# Sd_sdio.net
KiCad netlist of a schematic drawn in Altium Designer
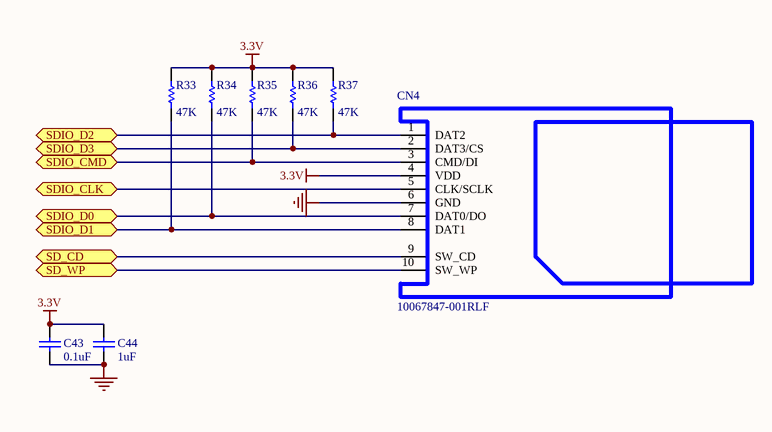
[diagram p0: Sd_sdio.SchDoc]

(export (version "E")
  (design (tool "Eeschema 10.0.6"))
  (components
    (comp (ref "C43")
      (value "0.1uF")
      (footprint "CAPC2012N")
      (description "Capacitor")
      (fields (field (name "Comment") "Cap"))
      (libsource (lib "Core429IBaseBoard") (part "Cap"))
    )
    (comp (ref "C44")
      (value "1uF")
      (footprint "CAPC3216N")
      (description "Capacitor")
      (fields (field (name "Comment") "Cap"))
      (libsource (lib "Core429IBaseBoard") (part "Cap"))
    )
    (comp (ref "CN4")
      (value "10067847-001RLF")
      (footprint "10067847")
      (description "SD Card Reader")
      (libsource (lib "Core429IBaseBoardVerE") (part "SD"))
    )
    (comp (ref "R33")
      (value "47K")
      (footprint "RESC2012N")
      (description "Resistor")
      (fields (field (name "Comment") "1206"))
      (libsource (lib "Core429IBaseBoard") (part "Res"))
    )
    (comp (ref "R34")
      (value "47K")
      (footprint "RESC2012N")
      (description "Resistor")
      (fields (field (name "Comment") "1206"))
      (libsource (lib "Core429IBaseBoard") (part "Res"))
    )
    (comp (ref "R35")
      (value "47K")
      (footprint "RESC2012N")
      (description "Resistor")
      (fields (field (name "Comment") "1206"))
      (libsource (lib "Core429IBaseBoard") (part "Res"))
    )
    (comp (ref "R36")
      (value "47K")
      (footprint "RESC2012N")
      (description "Resistor")
      (fields (field (name "Comment") "1206"))
      (libsource (lib "Core429IBaseBoard") (part "Res"))
    )
    (comp (ref "R37")
      (value "47K")
      (footprint "RESC2012N")
      (description "Resistor")
      (fields (field (name "Comment") "1206"))
      (libsource (lib "Core429IBaseBoard") (part "Res"))
    )
  )
  (nets
    (net (code "1") (name "/SDIO_CLK") (class "Default")
      (node (ref "CN4") (pin "5") (pinfunction "CLK/SCLK_5") (pintype "passive"))
    )
    (net (code "2") (name "/SDIO_CMD") (class "Default")
      (node (ref "CN4") (pin "3") (pinfunction "CMD/DI_3") (pintype "passive"))
      (node (ref "R35") (pin "1") (pinfunction "1_1") (pintype "passive"))
    )
    (net (code "3") (name "/SDIO_D0") (class "Default")
      (node (ref "CN4") (pin "7") (pinfunction "DAT0/DO_7") (pintype "passive"))
      (node (ref "R34") (pin "1") (pinfunction "1_1") (pintype "passive"))
    )
    (net (code "4") (name "/SDIO_D1") (class "Default")
      (node (ref "CN4") (pin "8") (pinfunction "DAT1_8") (pintype "passive"))
      (node (ref "R33") (pin "1") (pinfunction "1_1") (pintype "passive"))
    )
    (net (code "5") (name "/SDIO_D2") (class "Default")
      (node (ref "CN4") (pin "1") (pinfunction "DAT2_1") (pintype "passive"))
      (node (ref "R37") (pin "1") (pinfunction "1_1") (pintype "passive"))
    )
    (net (code "6") (name "/SDIO_D3") (class "Default")
      (node (ref "CN4") (pin "2") (pinfunction "DAT3/CS_2") (pintype "passive"))
      (node (ref "R36") (pin "1") (pinfunction "1_1") (pintype "passive"))
    )
    (net (code "7") (name "/SD_CD") (class "Default")
      (node (ref "CN4") (pin "9") (pinfunction "SW_CD_9") (pintype "passive"))
    )
    (net (code "8") (name "/SD_WP") (class "Default")
      (node (ref "CN4") (pin "10") (pinfunction "SW_WP_10") (pintype "passive"))
    )
    (net (code "9") (name "3.3V") (class "Default")
      (node (ref "C43") (pin "2") (pinfunction "2_2") (pintype "passive"))
      (node (ref "C44") (pin "2") (pinfunction "2_2") (pintype "passive"))
      (node (ref "CN4") (pin "4") (pinfunction "VDD_4") (pintype "passive"))
      (node (ref "R33") (pin "2") (pinfunction "2_2") (pintype "passive"))
      (node (ref "R34") (pin "2") (pinfunction "2_2") (pintype "passive"))
      (node (ref "R35") (pin "2") (pinfunction "2_2") (pintype "passive"))
      (node (ref "R36") (pin "2") (pinfunction "2_2") (pintype "passive"))
      (node (ref "R37") (pin "2") (pinfunction "2_2") (pintype "passive"))
    )
    (net (code "10") (name "DGND") (class "Default")
      (node (ref "C43") (pin "1") (pinfunction "1_1") (pintype "passive"))
      (node (ref "C44") (pin "1") (pinfunction "1_1") (pintype "passive"))
      (node (ref "CN4") (pin "6") (pinfunction "GND_6") (pintype "passive"))
    )
  )
)
